# Schematic_Rev2.net
KiCad netlist of a schematic drawn in Altium Designer
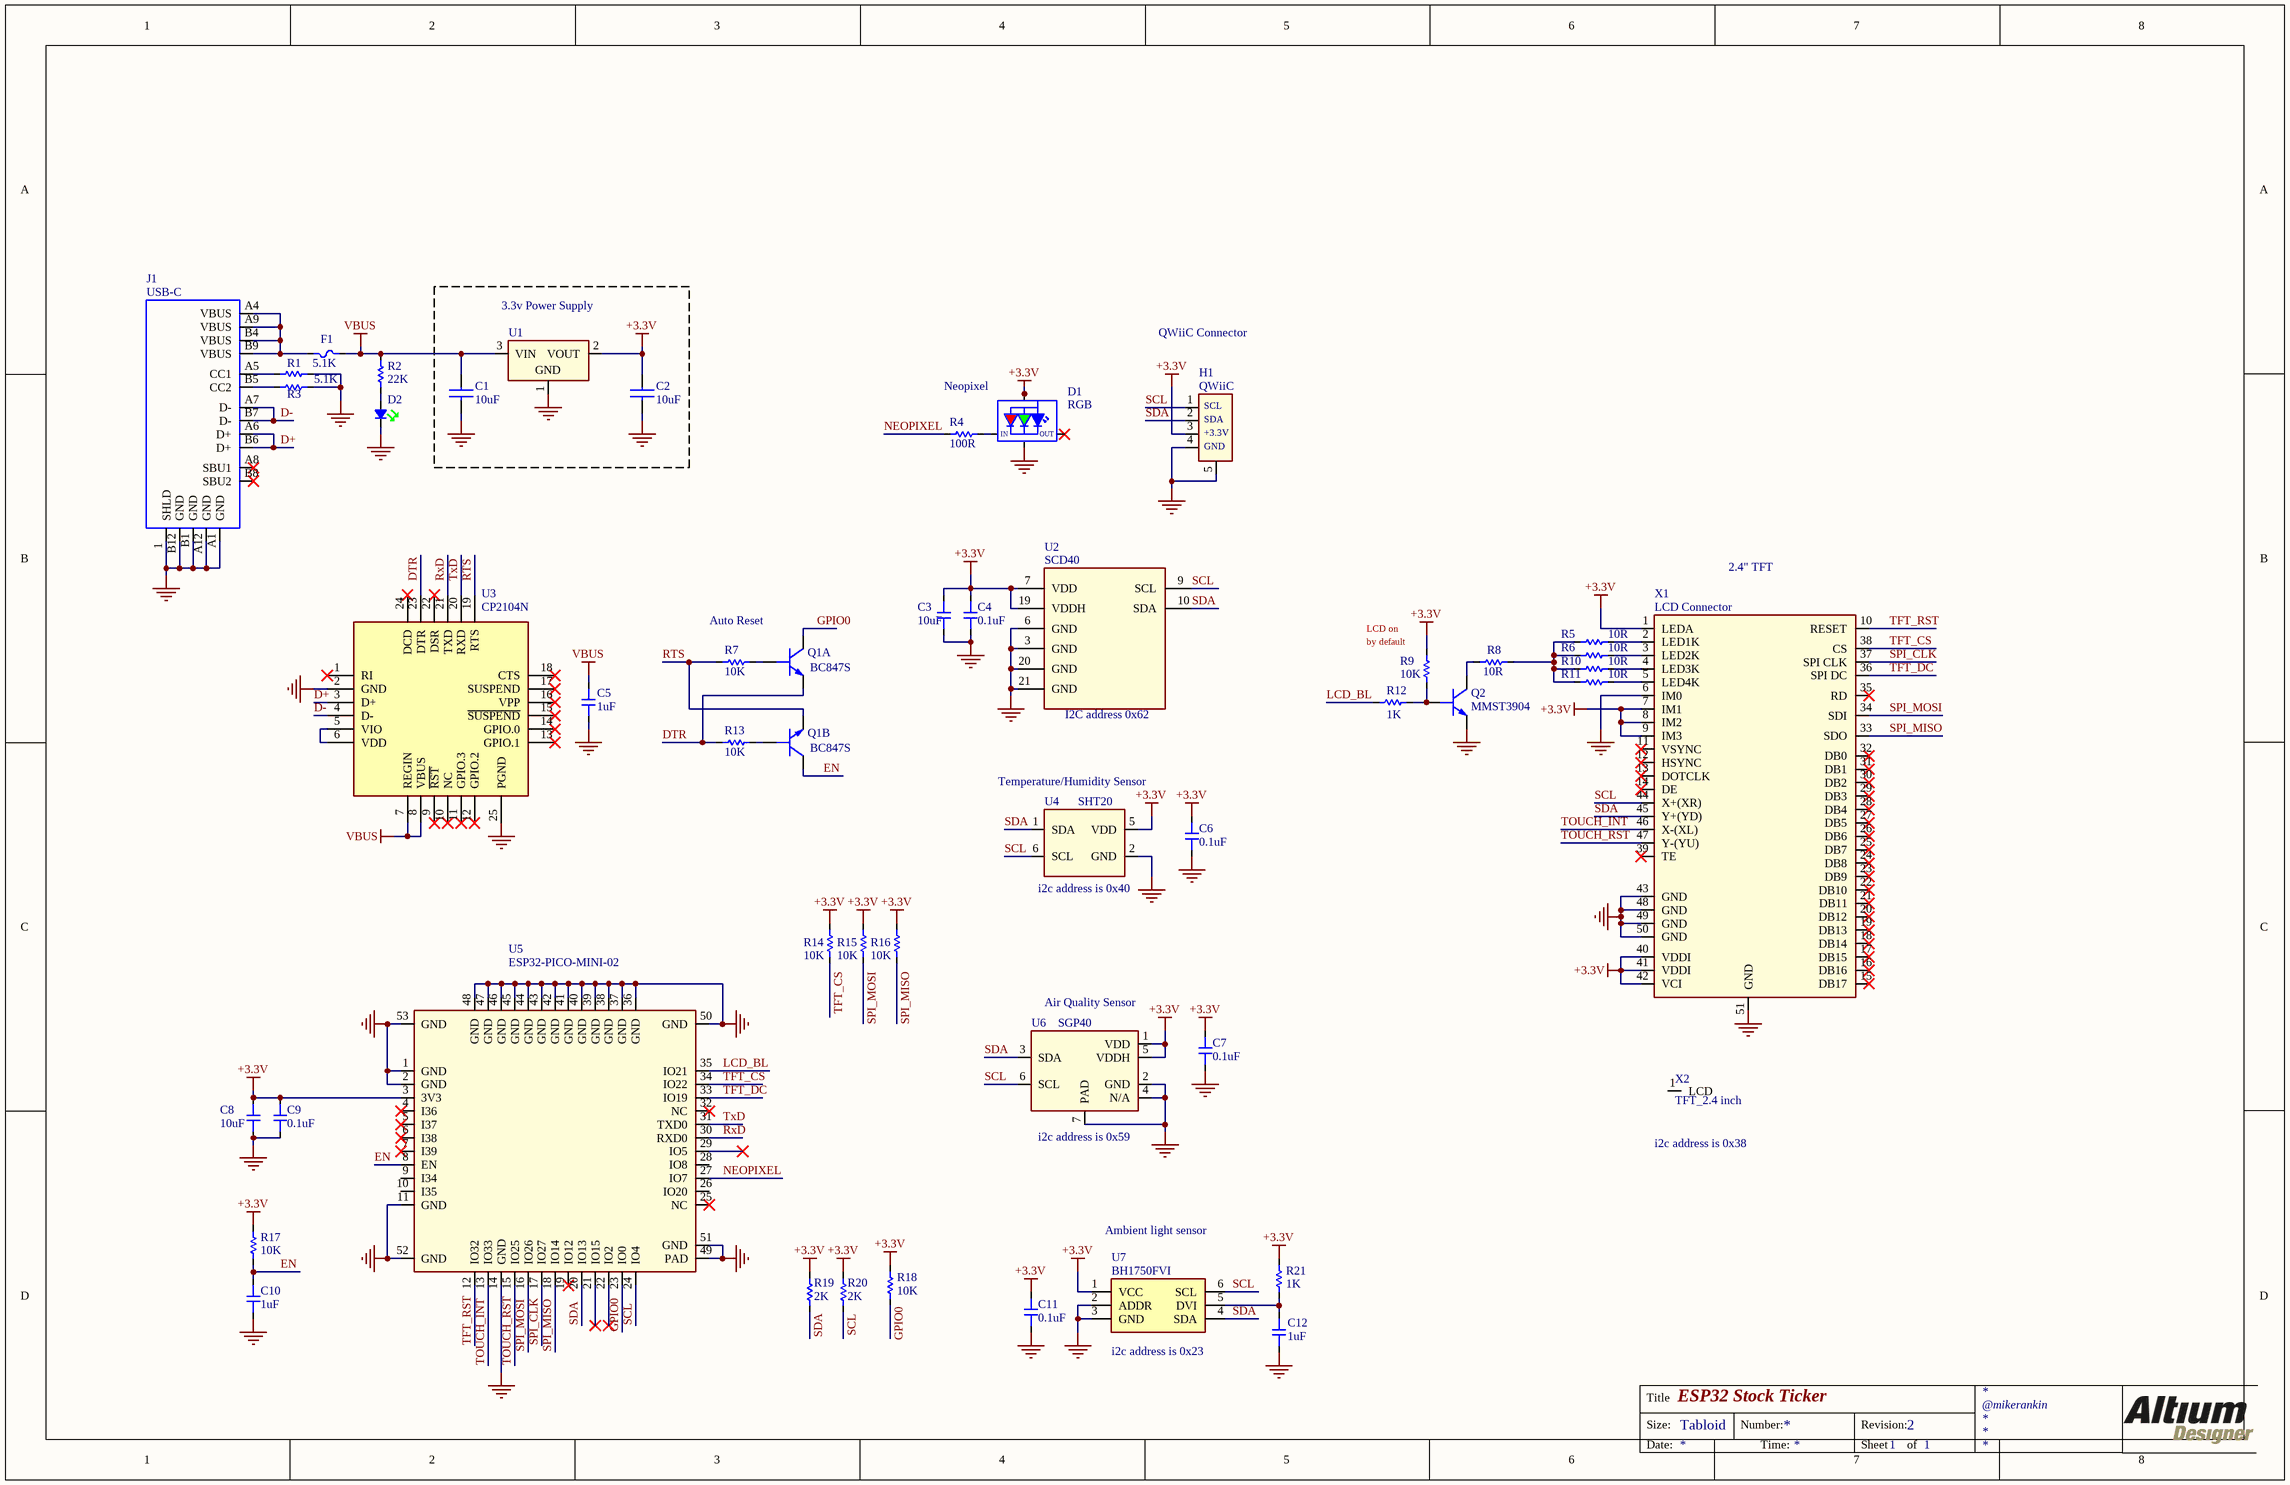
[diagram p0: Schematic_Rev2.SchDoc]

(export (version "E")
  (design (tool "Eeschema 10.0.6"))
  (components
    (comp (ref "C1")
      (value "10uF")
      (footprint "CAPC2012X140N")
      (description "CAP 10uF 16V 0805")
      (fields (field (name "PART_NUMBER") "C162317") (field (name "MANUFACTURER") "Murata"))
      (libsource (lib "MAR") (part "CAP_0805"))
    )
    (comp (ref "C2")
      (value "10uF")
      (footprint "CAPC2012X140N")
      (description "CAP 10uF 16V 0805")
      (fields (field (name "PART_NUMBER") "C162317") (field (name "MANUFACTURER") "Murata"))
      (libsource (lib "MAR") (part "CAP_0805"))
    )
    (comp (ref "C3")
      (value "10uF")
      (footprint "CAPC2012X140N")
      (description "CAP 10uF 50V 0805")
      (libsource (lib "") (part "CAP_0805_1"))
    )
    (comp (ref "C4")
      (value "0.1uF")
      (footprint "CAPC1608X09L")
      (description "CAP 0.1uF 0603")
      (libsource (lib "MAR") (part "CAP_0603"))
    )
    (comp (ref "C5")
      (value "1uF")
      (footprint "CAPC1005X56N")
      (description "CAP 1uF 0402")
      (libsource (lib "MAR") (part "CAP_0402"))
    )
    (comp (ref "C6")
      (value "0.1uF")
      (footprint "CAPC1005X56N")
      (description "CAP 0.1uF 0402")
      (libsource (lib "MAR") (part "CAP_0402"))
    )
    (comp (ref "C7")
      (value "0.1uF")
      (footprint "CAPC1005X56N")
      (description "CAP 0.1uF 0402")
      (libsource (lib "MAR") (part "CAP_0402"))
    )
    (comp (ref "C8")
      (value "10uF")
      (footprint "CAPC2012X140N")
      (description "CAP 10uF 0805")
      (libsource (lib "") (part "CAP_0805_1"))
    )
    (comp (ref "C9")
      (value "0.1uF")
      (footprint "CAPC1608X09L")
      (description "CAP 0.1uF 0603")
      (libsource (lib "MAR") (part "CAP_0603"))
    )
    (comp (ref "C10")
      (value "1uF")
      (footprint "CAPC1005X56N")
      (description "CAP 1uF 0402")
      (libsource (lib "MAR") (part "CAP_0402"))
    )
    (comp (ref "C11")
      (value "0.1uF")
      (footprint "CAPC1005X56N")
      (description "CAP 0.1uF 0402")
      (libsource (lib "MAR") (part "CAP_0402"))
    )
    (comp (ref "C12")
      (value "1uF")
      (footprint "CAPC1005X56N")
      (description "CAP 1uF 0402")
      (libsource (lib "MAR") (part "CAP_0402"))
    )
    (comp (ref "D1")
      (value "RGB")
      (footprint "SK6805-EC14")
      (description "LED,RGB,NEOPIXEL,SK6805-EC14")
      (fields (field (name "PART_NUMBER") "C2909055") (field (name "MANUFACTURER") "OPSCO"))
      (libsource (lib "MAR") (part "SK6805-EC14"))
    )
    (comp (ref "D2")
      (value "Green Led")
      (footprint "LED1005X40N-Green")
      (description "LED Green 0402")
      (fields (field (name "PART_NUMBER") "C74338"))
      (libsource (lib "MAR") (part "LED_0402_SMALL_GREEN"))
    )
    (comp (ref "F1")
      (value "TLC-PSMD050")
      (footprint "PTC2012X70L")
      (description "PTC FUSE 500mA hold, 1A trip 0805 SMD")
      (fields (field (name "MANUFACTURER") "TLC") (field (name "LCSC_PART_NUMBER") "C261942"))
      (libsource (lib "MAR") (part "PTC_FUSE"))
    )
    (comp (ref "H1")
      (value "QWiiC")
      (footprint "SM04B-SRSS-TB")
      (description "CONN HEADER 4POS .100 R/A QWIIC")
      (fields (field (name "MANUFACTURER") "JST") (field (name "PART_NUMBER") "SM04B-SRSS-TB(LF)(SN)"))
      (libsource (lib "MAR") (part "SM04B-SRSS-TB"))
    )
    (comp (ref "J1")
      (value "USB-C")
      (footprint "TYPE-C-31-M-12")
      (description "CONN RECPT USB-C")
      (fields (field (name "MANUFACTURER") "KHE") (field (name "PART_NUMBER") "C165948"))
      (libsource (lib "MAR") (part "USB-C"))
    )
    (comp (ref "Q1")
      (value "BC847S")
      (footprint "SOT65P210X110-6N")
      (description "TRANS 2NPN 44V 0.1A SC-70-6")
      (fields (field (name "MANUFACTURER") "Changjiang") (field (name "PART_NUMBER") "BC847S"))
      (libsource (lib "MAR") (part "BC847S"))
    )
    (comp (ref "Q2")
      (value "MMST3904")
      (footprint "SC-70")
      (description "TRANSISTOR NPN GP 40V SC-70")
      (fields (field (name "MANUFACTURER") "Changjiang") (field (name "PART_NUMBER") "C54879"))
      (libsource (lib "MAR") (part "MMST3904"))
    )
    (comp (ref "R1")
      (value "5.1K")
      (footprint "RESC1005X40L (0402 FOOTPRINT)")
      (description "RES 5.1K 0402")
      (libsource (lib "MAR") (part "RES_0603"))
    )
    (comp (ref "R2")
      (value "22K")
      (footprint "RESC1005X40L (0402 FOOTPRINT)")
      (description "RES 22K 0402")
      (fields (field (name "MANUFACTURER") "LIZ Elec") (field (name "PART_NUMBER") "C100310"))
      (libsource (lib "MAR") (part "RES_0603"))
    )
    (comp (ref "R3")
      (value "5.1K")
      (footprint "RESC1005X40L (0402 FOOTPRINT)")
      (description "RES 5.1K 0402")
      (libsource (lib "MAR") (part "RES_0603"))
    )
    (comp (ref "R4")
      (value "100R")
      (footprint "RESC1005X40L (0402 FOOTPRINT)")
      (description "RES 100R 0402")
      (libsource (lib "MAR") (part "RES_0402"))
    )
    (comp (ref "R5")
      (value "10R")
      (footprint "RESC1005X40L (0402 FOOTPRINT)")
      (description "RES 10R 0402")
      (libsource (lib "MAR") (part "RES_0402"))
    )
    (comp (ref "R6")
      (value "10R")
      (footprint "RESC1005X40L (0402 FOOTPRINT)")
      (description "RES 10R 0402")
      (libsource (lib "MAR") (part "RES_0402"))
    )
    (comp (ref "R7")
      (value "10K")
      (footprint "RESC1005X40L (0402 FOOTPRINT)")
      (description "RES 10K 0402")
      (libsource (lib "MAR") (part "RES_0402"))
    )
    (comp (ref "R8")
      (value "10R")
      (footprint "RESC1005X40L (0402 FOOTPRINT)")
      (description "RES 10R 0402")
      (libsource (lib "MAR") (part "RES_0402"))
    )
    (comp (ref "R9")
      (value "10K")
      (footprint "RESC1005X40L (0402 FOOTPRINT)")
      (description "RES 10K 0402")
      (libsource (lib "MAR") (part "RES_0402"))
    )
    (comp (ref "R10")
      (value "10R")
      (footprint "RESC1005X40L (0402 FOOTPRINT)")
      (description "RES 10R 0402")
      (libsource (lib "MAR") (part "RES_0402"))
    )
    (comp (ref "R11")
      (value "10R")
      (footprint "RESC1005X40L (0402 FOOTPRINT)")
      (description "RES 10R 0402")
      (libsource (lib "MAR") (part "RES_0402"))
    )
    (comp (ref "R12")
      (value "1K")
      (footprint "RESC1005X40L (0402 FOOTPRINT)")
      (description "RES 1K 0402")
      (libsource (lib "MAR") (part "RES_0402"))
    )
    (comp (ref "R13")
      (value "10K")
      (footprint "RESC1005X40L (0402 FOOTPRINT)")
      (description "RES 10K 0402")
      (libsource (lib "MAR") (part "RES_0402"))
    )
    (comp (ref "R14")
      (value "10K")
      (footprint "RESC1005X40L (0402 FOOTPRINT)")
      (description "RES 10K 0402")
      (libsource (lib "MAR") (part "RES_0402"))
    )
    (comp (ref "R15")
      (value "10K")
      (footprint "RESC1005X40L (0402 FOOTPRINT)")
      (description "RES 10K 0402")
      (libsource (lib "MAR") (part "RES_0402"))
    )
    (comp (ref "R16")
      (value "10K")
      (footprint "RESC1005X40L (0402 FOOTPRINT)")
      (description "RES 10K 0402")
      (libsource (lib "MAR") (part "RES_0402"))
    )
    (comp (ref "R17")
      (value "10K")
      (footprint "RESC1005X40L (0402 FOOTPRINT)")
      (description "RES 10K 0402")
      (libsource (lib "MAR") (part "RES_0402"))
    )
    (comp (ref "R18")
      (value "10K")
      (footprint "RESC1005X40L (0402 FOOTPRINT)")
      (description "RES 10K 0402")
      (libsource (lib "MAR") (part "RES_0402"))
    )
    (comp (ref "R19")
      (value "2K")
      (footprint "RESC1005X40L (0402 FOOTPRINT)")
      (description "RES 2K 0402")
      (libsource (lib "MAR") (part "RES_0402"))
    )
    (comp (ref "R20")
      (value "2K")
      (footprint "RESC1005X40L (0402 FOOTPRINT)")
      (description "RES 2K 0402")
      (libsource (lib "MAR") (part "RES_0402"))
    )
    (comp (ref "R21")
      (value "1K")
      (footprint "RESC1005X40L (0402 FOOTPRINT)")
      (description "RES 1K 0402")
      (libsource (lib "MAR") (part "RES_0402"))
    )
    (comp (ref "U1")
      (value "NCP1117LPST33T3G")
      (footprint "SOT230P700X180-4N")
      (description "IC REG LDO 3.3V 1A SOT223-3")
      (fields (field (name "MANUFACTURER") "ON Semi"))
      (libsource (lib "MAR") (part "NCP1117LPST33T3G"))
    )
    (comp (ref "U2")
      (value "SCD40")
      (footprint "SCD40")
      (description "CO2 SENSOR 50 PPM I2C SMD")
      (fields (field (name "MANUFACTURER") "Sensirion"))
      (libsource (lib "MAR") (part "SCD40"))
    )
    (comp (ref "U3")
      (value "CP2104N")
      (footprint "24-QFN")
      (description "IC BRIDGE USB TO UART 24QFN")
      (fields (field (name "MANUFACTURER") "Silicon Labs") (field (name "PART_NUMBER") "C47742"))
      (libsource (lib "MAR") (part "CP2104N"))
    )
    (comp (ref "U4")
      (value "SHT20")
      (footprint "DFN-6 (3mm X 3mm)")
      (description "SENSOR HUMID/TEMP 3V I2C 3% SMD")
      (fields (field (name "MANUFACTURER") "Sensirion AG"))
      (libsource (lib "MAR") (part "SHT20"))
    )
    (comp (ref "U5")
      (value "ESP32-PICO-MINI-02")
      (footprint "ESP32-PICO-MINI-02")
      (description "WIFI/Bluetooth, Mini Module")
      (fields (field (name "MANUFACTURER") "Espressif"))
      (libsource (lib "MAR") (part "ESP32-PICO-MINI-02"))
    )
    (comp (ref "U6")
      (value "SGP40")
      (footprint "DFN-6 (2.45mm X 2.45mm)")
      (description "AIR QUALITY GAS SENSOR FOR VOC'S")
      (fields (field (name "MANUFACTURER") "Sensirion AG") (field (name "PART_NUMBER") "SGP40-D-R4"))
      (libsource (lib "MAR") (part "SGP40"))
    )
    (comp (ref "U7")
      (value "BH1750FVI")
      (footprint "WSOF-6")
      (description "Optical Sensor Ambient I2C 6-SMD")
      (fields (field (name "MANUFACTURER") "Rohm") (field (name "PART_NUMBER") "C78960"))
      (libsource (lib "MAR") (part "BH1750FVI"))
    )
    (comp (ref "X1")
      (value "LCD Connector")
      (footprint "ER-CON50HT")
      (description "FFC, FPC 50 pin 0.5mm Connector for 2.4\" TFT")
      (fields (field (name "PART_NUMBER") "C397332") (field (name "MANUFACTURER") "XKB"))
      (libsource (lib "MAR") (part "FFC, FPC 50 pin 0.5mm Con 2.4{dblquote} TFT"))
    )
    (comp (ref "X2")
      (value "TFT_2.4 inch")
      (description "2.4 INCH TFT GLASS COLOR")
      (fields (field (name "PART_NUMBER") "ER-TFT024-3") (field (name "MANUFACTURER") "BuyDisplay.com"))
      (libsource (lib "MAR") (part "TFT_GLASS 2.4 INCH COLOR"))
    )
  )
  (nets
    (net (code "1") (name "+3.3V") (class "Default")
      (node (ref "C11") (pin "1") (pintype "passive"))
      (node (ref "C2") (pin "1") (pinfunction "1_1") (pintype "passive"))
      (node (ref "C3") (pin "1") (pintype "passive"))
      (node (ref "C4") (pin "1") (pintype "passive"))
      (node (ref "C6") (pin "1") (pintype "passive"))
      (node (ref "C7") (pin "1") (pintype "passive"))
      (node (ref "C8") (pin "1") (pintype "passive"))
      (node (ref "C9") (pin "1") (pintype "passive"))
      (node (ref "D1") (pin "1") (pinfunction "VDD_1") (pintype "passive"))
      (node (ref "H1") (pin "3") (pintype "passive"))
      (node (ref "R14") (pin "1") (pintype "passive"))
      (node (ref "R15") (pin "1") (pintype "passive"))
      (node (ref "R16") (pin "1") (pintype "passive"))
      (node (ref "R17") (pin "2") (pintype "passive"))
      (node (ref "R18") (pin "2") (pintype "passive"))
      (node (ref "R19") (pin "1") (pintype "passive"))
      (node (ref "R20") (pin "1") (pintype "passive"))
      (node (ref "R21") (pin "2") (pintype "passive"))
      (node (ref "R9") (pin "1") (pintype "passive"))
      (node (ref "U1") (pin "2") (pinfunction "VOUT_2") (pintype "power_in"))
      (node (ref "U2") (pin "19") (pinfunction "VDDH_19") (pintype "power_in"))
      (node (ref "U2") (pin "7") (pinfunction "VDD_7") (pintype "power_in"))
      (node (ref "U4") (pin "5") (pinfunction "VDD_5") (pintype "power_in"))
      (node (ref "U5") (pin "3") (pinfunction "3V3_3") (pintype "power_in"))
      (node (ref "U6") (pin "1") (pinfunction "VDD_1") (pintype "power_in"))
      (node (ref "U6") (pin "5") (pinfunction "VDDH_5") (pintype "power_in"))
      (node (ref "U7") (pin "1") (pinfunction "VCC_1") (pintype "power_in"))
      (node (ref "X1") (pin "1") (pinfunction "LEDA_1") (pintype "passive"))
      (node (ref "X1") (pin "40") (pinfunction "VDDI_40") (pintype "power_in"))
      (node (ref "X1") (pin "41") (pinfunction "VDDI_41") (pintype "open_emitter"))
      (node (ref "X1") (pin "42") (pinfunction "VCI_42") (pintype "power_in"))
      (node (ref "X1") (pin "7") (pinfunction "IM1_7") (pintype "passive"))
      (node (ref "X1") (pin "8") (pinfunction "IM2_8") (pintype "passive"))
      (node (ref "X1") (pin "9") (pinfunction "IM3_9") (pintype "passive"))
    )
    (net (code "2") (name "/D+") (class "Default")
      (node (ref "J1") (pin "A6") (pinfunction "D+_A6") (pintype "power_in"))
      (node (ref "J1") (pin "B6") (pinfunction "D+_B6") (pintype "power_in"))
      (node (ref "U3") (pin "3") (pinfunction "D+_3") (pintype "passive"))
    )
    (net (code "3") (name "/D-") (class "Default")
      (node (ref "J1") (pin "A7") (pinfunction "D-_A7") (pintype "power_in"))
      (node (ref "J1") (pin "B7") (pinfunction "D-_B7") (pintype "power_in"))
      (node (ref "U3") (pin "4") (pinfunction "D-_4") (pintype "passive"))
    )
    (net (code "4") (name "/DTR") (class "Default")
      (node (ref "Q1") (pin "1") (pinfunction "E1_1") (pintype "passive"))
      (node (ref "R13") (pin "2") (pintype "passive"))
      (node (ref "U3") (pin "23") (pinfunction "DTR_23") (pintype "passive"))
    )
    (net (code "5") (name "/EN") (class "Default")
      (node (ref "C10") (pin "1") (pintype "passive"))
      (node (ref "Q1") (pin "3") (pinfunction "C2_3") (pintype "passive"))
      (node (ref "R17") (pin "1") (pintype "passive"))
      (node (ref "U5") (pin "8") (pinfunction "EN_8") (pintype "passive"))
    )
    (net (code "6") (name "/GPIO0") (class "Default")
      (node (ref "Q1") (pin "6") (pinfunction "C1_6") (pintype "passive"))
      (node (ref "R18") (pin "1") (pintype "passive"))
      (node (ref "U5") (pin "23") (pinfunction "IO0_23") (pintype "passive"))
    )
    (net (code "7") (name "/LCD_BL") (class "Default")
      (node (ref "R12") (pin "2") (pintype "passive"))
      (node (ref "U5") (pin "35") (pinfunction "IO21_35") (pintype "passive"))
    )
    (net (code "8") (name "/NEOPIXEL") (class "Default")
      (node (ref "R4") (pin "2") (pintype "passive"))
      (node (ref "U5") (pin "27") (pinfunction "IO7_27") (pintype "passive"))
    )
    (net (code "9") (name "/RTS") (class "Default")
      (node (ref "Q1") (pin "4") (pinfunction "E2_4") (pintype "passive"))
      (node (ref "R7") (pin "2") (pintype "passive"))
      (node (ref "U3") (pin "19") (pinfunction "RTS_19") (pintype "passive"))
    )
    (net (code "10") (name "/RxD") (class "Default")
      (node (ref "U3") (pin "21") (pinfunction "TXD_21") (pintype "passive"))
      (node (ref "U5") (pin "30") (pinfunction "RXD0_30") (pintype "passive"))
    )
    (net (code "11") (name "/SCL") (class "Default")
      (node (ref "H1") (pin "1") (pintype "passive"))
      (node (ref "R20") (pin "2") (pintype "passive"))
      (node (ref "U2") (pin "9") (pinfunction "SCL_9") (pintype "passive"))
      (node (ref "U4") (pin "6") (pinfunction "SCL_6") (pintype "passive"))
      (node (ref "U5") (pin "24") (pinfunction "IO4_24") (pintype "passive"))
      (node (ref "U6") (pin "6") (pinfunction "SCL_6") (pintype "passive"))
      (node (ref "U7") (pin "6") (pinfunction "SCL_6") (pintype "passive"))
      (node (ref "X1") (pin "44") (pinfunction "X+(XR)_44") (pintype "passive"))
    )
    (net (code "12") (name "/SDA") (class "Default")
      (node (ref "H1") (pin "2") (pintype "passive"))
      (node (ref "R19") (pin "2") (pintype "passive"))
      (node (ref "U2") (pin "10") (pinfunction "SDA_10") (pintype "passive"))
      (node (ref "U4") (pin "1") (pinfunction "SDA_1") (pintype "passive"))
      (node (ref "U5") (pin "20") (pinfunction "IO13_20") (pintype "passive"))
      (node (ref "U6") (pin "3") (pinfunction "SDA_3") (pintype "passive"))
      (node (ref "U7") (pin "4") (pinfunction "SDA_4") (pintype "passive"))
      (node (ref "X1") (pin "45") (pinfunction "Y+(YD)_45") (pintype "passive"))
    )
    (net (code "13") (name "/SPI_CLK") (class "Default")
      (node (ref "U5") (pin "17") (pinfunction "IO27_17") (pintype "passive"))
      (node (ref "X1") (pin "37") (pinfunction "SPI_CLK_37") (pintype "passive"))
    )
    (net (code "14") (name "/SPI_MISO") (class "Default")
      (node (ref "R16") (pin "2") (pintype "passive"))
      (node (ref "U5") (pin "18") (pinfunction "IO14_18") (pintype "passive"))
      (node (ref "X1") (pin "33") (pinfunction "SDO_33") (pintype "passive"))
    )
    (net (code "15") (name "/SPI_MOSI") (class "Default")
      (node (ref "R15") (pin "2") (pintype "passive"))
      (node (ref "U5") (pin "16") (pinfunction "IO26_16") (pintype "passive"))
      (node (ref "X1") (pin "34") (pinfunction "SDI_34") (pintype "passive"))
    )
    (net (code "16") (name "/TFT_CS") (class "Default")
      (node (ref "R14") (pin "2") (pintype "passive"))
      (node (ref "U5") (pin "34") (pinfunction "IO22_34") (pintype "passive"))
      (node (ref "X1") (pin "38") (pinfunction "CS_38") (pintype "passive"))
    )
    (net (code "17") (name "/TFT_DC") (class "Default")
      (node (ref "U5") (pin "33") (pinfunction "IO19_33") (pintype "passive"))
      (node (ref "X1") (pin "36") (pinfunction "SPI_DC_36") (pintype "passive"))
    )
    (net (code "18") (name "/TFT_RST") (class "Default")
      (node (ref "U5") (pin "12") (pinfunction "IO32_12") (pintype "passive"))
      (node (ref "X1") (pin "10") (pinfunction "RESET_10") (pintype "passive"))
    )
    (net (code "19") (name "/TOUCH_INT") (class "Default")
      (node (ref "U5") (pin "13") (pinfunction "IO33_13") (pintype "passive"))
      (node (ref "X1") (pin "46") (pinfunction "X-(XL)_46") (pintype "passive"))
    )
    (net (code "20") (name "/TOUCH_RST") (class "Default")
      (node (ref "U5") (pin "15") (pinfunction "IO25_15") (pintype "passive"))
      (node (ref "X1") (pin "47") (pinfunction "Y-(YU)_47") (pintype "passive"))
    )
    (net (code "21") (name "/TxD") (class "Default")
      (node (ref "U3") (pin "20") (pinfunction "RXD_20") (pintype "passive"))
      (node (ref "U5") (pin "31") (pinfunction "TXD0_31") (pintype "passive"))
    )
    (net (code "22") (name "GND") (class "Default")
      (node (ref "C1") (pin "2") (pinfunction "2_2") (pintype "passive"))
      (node (ref "C10") (pin "2") (pintype "passive"))
      (node (ref "C11") (pin "2") (pintype "passive"))
      (node (ref "C12") (pin "1") (pintype "passive"))
      (node (ref "C2") (pin "2") (pinfunction "2_2") (pintype "passive"))
      (node (ref "C3") (pin "2") (pintype "passive"))
      (node (ref "C4") (pin "2") (pintype "passive"))
      (node (ref "C5") (pin "1") (pintype "passive"))
      (node (ref "C6") (pin "2") (pintype "passive"))
      (node (ref "C7") (pin "2") (pintype "passive"))
      (node (ref "C8") (pin "2") (pintype "passive"))
      (node (ref "C9") (pin "2") (pintype "passive"))
      (node (ref "D1") (pin "3") (pinfunction "GND_3") (pintype "passive"))
      (node (ref "D2") (pin "1") (pintype "passive"))
      (node (ref "H1") (pin "4") (pintype "passive"))
      (node (ref "H1") (pin "5") (pintype "passive"))
      (node (ref "J1") (pin "1") (pinfunction "SHLD_1") (pintype "power_in"))
      (node (ref "J1") (pin "A1") (pinfunction "GND_A1") (pintype "power_in"))
      (node (ref "J1") (pin "A12") (pinfunction "GND_A12") (pintype "power_in"))
      (node (ref "J1") (pin "B1") (pinfunction "GND_B1") (pintype "power_in"))
      (node (ref "J1") (pin "B12") (pinfunction "GND_B12") (pintype "passive"))
      (node (ref "Q2") (pin "2") (pinfunction "E_2") (pintype "passive"))
      (node (ref "R1") (pin "2") (pintype "passive"))
      (node (ref "R3") (pin "2") (pintype "passive"))
      (node (ref "U1") (pin "1") (pinfunction "GND_1") (pintype "power_in"))
      (node (ref "U2") (pin "20") (pinfunction "GND_20") (pintype "power_in"))
      (node (ref "U2") (pin "21") (pinfunction "GND_21") (pintype "power_in"))
      (node (ref "U2") (pin "3") (pinfunction "GND_3") (pintype "power_in"))
      (node (ref "U2") (pin "6") (pinfunction "GND_6") (pintype "power_in"))
      (node (ref "U3") (pin "2") (pinfunction "GND_2") (pintype "power_in"))
      (node (ref "U3") (pin "25") (pinfunction "PGND_25") (pintype "passive"))
      (node (ref "U4") (pin "2") (pinfunction "GND_2") (pintype "power_in"))
      (node (ref "U5") (pin "1") (pinfunction "GND_1") (pintype "power_in"))
      (node (ref "U5") (pin "11") (pinfunction "GND_11") (pintype "power_in"))
      (node (ref "U5") (pin "14") (pinfunction "GND_14") (pintype "power_in"))
      (node (ref "U5") (pin "2") (pinfunction "GND_2") (pintype "power_in"))
      (node (ref "U5") (pin "36") (pinfunction "GND_36") (pintype "power_in"))
      (node (ref "U5") (pin "37") (pinfunction "GND_37") (pintype "power_in"))
      (node (ref "U5") (pin "38") (pinfunction "GND_38") (pintype "power_in"))
      (node (ref "U5") (pin "39") (pinfunction "GND_39") (pintype "power_in"))
      (node (ref "U5") (pin "40") (pinfunction "GND_40") (pintype "power_in"))
      (node (ref "U5") (pin "41") (pinfunction "GND_41") (pintype "power_in"))
      (node (ref "U5") (pin "42") (pinfunction "GND_42") (pintype "power_in"))
      (node (ref "U5") (pin "43") (pinfunction "GND_43") (pintype "power_in"))
      (node (ref "U5") (pin "44") (pinfunction "GND_44") (pintype "power_in"))
      (node (ref "U5") (pin "45") (pinfunction "GND_45") (pintype "power_in"))
      (node (ref "U5") (pin "46") (pinfunction "GND_46") (pintype "power_in"))
      (node (ref "U5") (pin "47") (pinfunction "GND_47") (pintype "power_in"))
      (node (ref "U5") (pin "48") (pinfunction "GND_48") (pintype "power_in"))
      (node (ref "U5") (pin "49") (pinfunction "PAD_49") (pintype "power_in"))
      (node (ref "U5") (pin "50") (pinfunction "GND_50") (pintype "power_in"))
      (node (ref "U5") (pin "51") (pinfunction "GND_51") (pintype "power_in"))
      (node (ref "U5") (pin "52") (pinfunction "GND_52") (pintype "power_in"))
      (node (ref "U5") (pin "53") (pinfunction "GND_53") (pintype "power_in"))
      (node (ref "U6") (pin "2") (pinfunction "GND_2") (pintype "power_in"))
      (node (ref "U6") (pin "4") (pinfunction "N/A_4") (pintype "passive"))
      (node (ref "U6") (pin "7") (pinfunction "PAD_7") (pintype "passive"))
      (node (ref "U7") (pin "2") (pinfunction "ADDR_2") (pintype "passive"))
      (node (ref "U7") (pin "3") (pinfunction "GND_3") (pintype "power_in"))
      (node (ref "X1") (pin "43") (pinfunction "GND_43") (pintype "power_in"))
      (node (ref "X1") (pin "48") (pinfunction "GND_48") (pintype "power_in"))
      (node (ref "X1") (pin "49") (pinfunction "GND_49") (pintype "power_in"))
      (node (ref "X1") (pin "50") (pinfunction "GND_50") (pintype "power_in"))
      (node (ref "X1") (pin "51") (pinfunction "GND_51") (pintype "power_in"))
      (node (ref "X1") (pin "6") (pinfunction "IM0_6") (pintype "passive"))
    )
    (net (code "23") (name "Net-(D1-DIN)") (class "Default")
      (node (ref "D1") (pin "4") (pinfunction "DIN_4") (pintype "passive"))
      (node (ref "R4") (pin "1") (pintype "passive"))
    )
    (net (code "24") (name "Net-(D2-Pad2)") (class "Default")
      (node (ref "D2") (pin "2") (pintype "passive"))
      (node (ref "R2") (pin "1") (pintype "passive"))
    )
    (net (code "25") (name "Net-(F1-Pad2)") (class "Default")
      (node (ref "F1") (pin "2") (pintype "passive"))
      (node (ref "J1") (pin "A4") (pinfunction "VBUS_A4") (pintype "passive"))
      (node (ref "J1") (pin "A9") (pinfunction "VBUS_A9") (pintype "power_in"))
      (node (ref "J1") (pin "B4") (pinfunction "VBUS_B4") (pintype "power_in"))
      (node (ref "J1") (pin "B9") (pinfunction "VBUS_B9") (pintype "passive"))
    )
    (net (code "26") (name "Net-(J1-CC1)") (class "Default")
      (node (ref "J1") (pin "A5") (pinfunction "CC1_A5") (pintype "power_in"))
      (node (ref "R1") (pin "1") (pintype "passive"))
    )
    (net (code "27") (name "Net-(J1-CC2)") (class "Default")
      (node (ref "J1") (pin "B5") (pinfunction "CC2_B5") (pintype "power_in"))
      (node (ref "R3") (pin "1") (pintype "passive"))
    )
    (net (code "28") (name "Net-(Q1A-B1)") (class "Default")
      (node (ref "Q1") (pin "2") (pinfunction "B1_2") (pintype "passive"))
      (node (ref "R7") (pin "1") (pintype "passive"))
    )
    (net (code "29") (name "Net-(Q1B-B2)") (class "Default")
      (node (ref "Q1") (pin "5") (pinfunction "B2_5") (pintype "passive"))
      (node (ref "R13") (pin "1") (pintype "passive"))
    )
    (net (code "30") (name "Net-(Q2-B)") (class "Default")
      (node (ref "Q2") (pin "1") (pinfunction "B_1") (pintype "passive"))
      (node (ref "R12") (pin "1") (pintype "passive"))
      (node (ref "R9") (pin "2") (pintype "passive"))
    )
    (net (code "31") (name "Net-(Q2-C)") (class "Default")
      (node (ref "Q2") (pin "3") (pinfunction "C_3") (pintype "passive"))
      (node (ref "R8") (pin "2") (pintype "passive"))
    )
    (net (code "32") (name "Net-(R10-Pad2)") (class "Default")
      (node (ref "R10") (pin "2") (pintype "passive"))
      (node (ref "R11") (pin "2") (pintype "passive"))
      (node (ref "R5") (pin "2") (pintype "passive"))
      (node (ref "R6") (pin "2") (pintype "passive"))
      (node (ref "R8") (pin "1") (pintype "passive"))
    )
    (net (code "33") (name "Net-(U3-VDD)") (class "Default")
      (node (ref "U3") (pin "5") (pinfunction "VIO_5") (pintype "power_in"))
      (node (ref "U3") (pin "6") (pinfunction "VDD_6") (pintype "power_in"))
    )
    (net (code "34") (name "Net-(U7-DVI)") (class "Default")
      (node (ref "C12") (pin "2") (pintype "passive"))
      (node (ref "R21") (pin "1") (pintype "passive"))
      (node (ref "U7") (pin "5") (pinfunction "DVI_5") (pintype "passive"))
    )
    (net (code "35") (name "Net-(X1-LED1K)") (class "Default")
      (node (ref "R5") (pin "1") (pintype "passive"))
      (node (ref "X1") (pin "2") (pinfunction "LED1K_2") (pintype "passive"))
    )
    (net (code "36") (name "Net-(X1-LED2K)") (class "Default")
      (node (ref "R6") (pin "1") (pintype "passive"))
      (node (ref "X1") (pin "3") (pinfunction "LED2K_3") (pintype "passive"))
    )
    (net (code "37") (name "Net-(X1-LED3K)") (class "Default")
      (node (ref "R10") (pin "1") (pintype "passive"))
      (node (ref "X1") (pin "4") (pinfunction "LED3K_4") (pintype "passive"))
    )
    (net (code "38") (name "Net-(X1-LED4K)") (class "Default")
      (node (ref "R11") (pin "1") (pintype "passive"))
      (node (ref "X1") (pin "5") (pinfunction "LED4K_5") (pintype "passive"))
    )
    (net (code "39") (name "VBUS") (class "Default")
      (node (ref "C1") (pin "1") (pinfunction "1_1") (pintype "passive"))
      (node (ref "C5") (pin "2") (pintype "passive"))
      (node (ref "F1") (pin "1") (pintype "passive"))
      (node (ref "R2") (pin "2") (pintype "passive"))
      (node (ref "U1") (pin "3") (pinfunction "VIN_3") (pintype "power_in"))
      (node (ref "U3") (pin "7") (pinfunction "REGIN_7") (pintype "power_in"))
      (node (ref "U3") (pin "8") (pinfunction "VBUS_8") (pintype "power_in"))
    )
    (net (code "40") (name "unconnected-(D1-DOUT-Pad2)") (class "Default")
      (node (ref "D1") (pin "2") (pinfunction "DOUT_2") (pintype "passive+no_connect"))
    )
    (net (code "41") (name "unconnected-(J1-SBU1-PadA8)") (class "Default")
      (node (ref "J1") (pin "A8") (pinfunction "SBU1_A8") (pintype "power_in+no_connect"))
    )
    (net (code "42") (name "unconnected-(J1-SBU2-PadB8)") (class "Default")
      (node (ref "J1") (pin "B8") (pinfunction "SBU2_B8") (pintype "power_in+no_connect"))
    )
    (net (code "43") (name "unconnected-(U3-CTS-Pad18)") (class "Default")
      (node (ref "U3") (pin "18") (pinfunction "CTS_18") (pintype "passive+no_connect"))
    )
    (net (code "44") (name "unconnected-(U3-DCD-Pad24)") (class "Default")
      (node (ref "U3") (pin "24") (pinfunction "DCD_24") (pintype "passive+no_connect"))
    )
    (net (code "45") (name "unconnected-(U3-DSR-Pad22)") (class "Default")
      (node (ref "U3") (pin "22") (pinfunction "DSR_22") (pintype "passive+no_connect"))
    )
    (net (code "46") (name "unconnected-(U3-GPIO.0-Pad14)") (class "Default")
      (node (ref "U3") (pin "14") (pinfunction "GPIO.0_14") (pintype "passive+no_connect"))
    )
    (net (code "47") (name "unconnected-(U3-GPIO.1-Pad13)") (class "Default")
      (node (ref "U3") (pin "13") (pinfunction "GPIO.1_13") (pintype "passive+no_connect"))
    )
    (net (code "48") (name "unconnected-(U3-GPIO.2-Pad12)") (class "Default")
      (node (ref "U3") (pin "12") (pinfunction "GPIO.2_12") (pintype "passive+no_connect"))
    )
    (net (code "49") (name "unconnected-(U3-GPIO.3-Pad11)") (class "Default")
      (node (ref "U3") (pin "11") (pinfunction "GPIO.3_11") (pintype "passive+no_connect"))
    )
    (net (code "50") (name "unconnected-(U3-NC-Pad10)") (class "Default")
      (node (ref "U3") (pin "10") (pinfunction "NC_10") (pintype "passive+no_connect"))
    )
    (net (code "51") (name "unconnected-(U3-RI-Pad1)") (class "Default")
      (node (ref "U3") (pin "1") (pinfunction "RI_1") (pintype "passive+no_connect"))
    )
    (net (code "52") (name "unconnected-(U3-SUSPEND-Pad17)") (class "Default")
      (node (ref "U3") (pin "17") (pinfunction "SUSPEND_17") (pintype "passive+no_connect"))
    )
    (net (code "53") (name "unconnected-(U3-VPP-Pad16)") (class "Default")
      (node (ref "U3") (pin "16") (pinfunction "VPP_16") (pintype "passive+no_connect"))
    )
    (net (code "54") (name "unconnected-(U3-~{RST}-Pad9)") (class "Default")
      (node (ref "U3") (pin "9") (pinfunction "~{RST}_9") (pintype "passive+no_connect"))
    )
    (net (code "55") (name "unconnected-(U3-~{SUSPEND}-Pad15)") (class "Default")
      (node (ref "U3") (pin "15") (pinfunction "~{SUSPEND}_15") (pintype "passive+no_connect"))
    )
    (net (code "56") (name "unconnected-(U5-I34-Pad9)") (class "Default")
      (node (ref "U5") (pin "9") (pinfunction "I34_9") (pintype "passive"))
    )
    (net (code "57") (name "unconnected-(U5-I35-Pad10)") (class "Default")
      (node (ref "U5") (pin "10") (pinfunction "I35_10") (pintype "passive"))
    )
    (net (code "58") (name "unconnected-(U5-I36-Pad4)") (class "Default")
      (node (ref "U5") (pin "4") (pinfunction "I36_4") (pintype "passive+no_connect"))
    )
    (net (code "59") (name "unconnected-(U5-I37-Pad5)") (class "Default")
      (node (ref "U5") (pin "5") (pinfunction "I37_5") (pintype "passive+no_connect"))
    )
    (net (code "60") (name "unconnected-(U5-I38-Pad6)") (class "Default")
      (node (ref "U5") (pin "6") (pinfunction "I38_6") (pintype "passive+no_connect"))
    )
    (net (code "61") (name "unconnected-(U5-I39-Pad7)") (class "Default")
      (node (ref "U5") (pin "7") (pinfunction "I39_7") (pintype "passive+no_connect"))
    )
    (net (code "62") (name "unconnected-(U5-IO2-Pad22)") (class "Default")
      (node (ref "U5") (pin "22") (pinfunction "IO2_22") (pintype "passive+no_connect"))
    )
    (net (code "63") (name "unconnected-(U5-IO5-Pad29)") (class "Default")
      (node (ref "U5") (pin "29") (pinfunction "IO5_29") (pintype "passive+no_connect"))
    )
    (net (code "64") (name "unconnected-(U5-IO8-Pad28)") (class "Default")
      (node (ref "U5") (pin "28") (pinfunction "IO8_28") (pintype "passive"))
    )
    (net (code "65") (name "unconnected-(U5-IO12-Pad19)") (class "Default")
      (node (ref "U5") (pin "19") (pinfunction "IO12_19") (pintype "passive+no_connect"))
    )
    (net (code "66") (name "unconnected-(U5-IO15-Pad21)") (class "Default")
      (node (ref "U5") (pin "21") (pinfunction "IO15_21") (pintype "passive+no_connect"))
    )
    (net (code "67") (name "unconnected-(U5-IO20-Pad26)") (class "Default")
      (node (ref "U5") (pin "26") (pinfunction "IO20_26") (pintype "power_in"))
    )
    (net (code "68") (name "unconnected-(U5-NC-Pad25)") (class "Default")
      (node (ref "U5") (pin "25") (pinfunction "NC_25") (pintype "passive+no_connect"))
    )
    (net (code "69") (name "unconnected-(U5-NC-Pad32)") (class "Default")
      (node (ref "U5") (pin "32") (pinfunction "NC_32") (pintype "passive+no_connect"))
    )
    (net (code "70") (name "unconnected-(X1-DB0-Pad32)") (class "Default")
      (node (ref "X1") (pin "32") (pinfunction "DB0_32") (pintype "passive+no_connect"))
    )
    (net (code "71") (name "unconnected-(X1-DB1-Pad31)") (class "Default")
      (node (ref "X1") (pin "31") (pinfunction "DB1_31") (pintype "passive+no_connect"))
    )
    (net (code "72") (name "unconnected-(X1-DB2-Pad30)") (class "Default")
      (node (ref "X1") (pin "30") (pinfunction "DB2_30") (pintype "passive+no_connect"))
    )
    (net (code "73") (name "unconnected-(X1-DB3-Pad29)") (class "Default")
      (node (ref "X1") (pin "29") (pinfunction "DB3_29") (pintype "passive+no_connect"))
    )
    (net (code "74") (name "unconnected-(X1-DB4-Pad28)") (class "Default")
      (node (ref "X1") (pin "28") (pinfunction "DB4_28") (pintype "passive+no_connect"))
    )
    (net (code "75") (name "unconnected-(X1-DB5-Pad27)") (class "Default")
      (node (ref "X1") (pin "27") (pinfunction "DB5_27") (pintype "passive+no_connect"))
    )
    (net (code "76") (name "unconnected-(X1-DB6-Pad26)") (class "Default")
      (node (ref "X1") (pin "26") (pinfunction "DB6_26") (pintype "passive+no_connect"))
    )
    (net (code "77") (name "unconnected-(X1-DB7-Pad25)") (class "Default")
      (node (ref "X1") (pin "25") (pinfunction "DB7_25") (pintype "passive+no_connect"))
    )
    (net (code "78") (name "unconnected-(X1-DB8-Pad24)") (class "Default")
      (node (ref "X1") (pin "24") (pinfunction "DB8_24") (pintype "passive+no_connect"))
    )
    (net (code "79") (name "unconnected-(X1-DB9-Pad23)") (class "Default")
      (node (ref "X1") (pin "23") (pinfunction "DB9_23") (pintype "passive+no_connect"))
    )
    (net (code "80") (name "unconnected-(X1-DB10-Pad22)") (class "Default")
      (node (ref "X1") (pin "22") (pinfunction "DB10_22") (pintype "passive+no_connect"))
    )
    (net (code "81") (name "unconnected-(X1-DB11-Pad21)") (class "Default")
      (node (ref "X1") (pin "21") (pinfunction "DB11_21") (pintype "passive+no_connect"))
    )
    (net (code "82") (name "unconnected-(X1-DB12-Pad20)") (class "Default")
      (node (ref "X1") (pin "20") (pinfunction "DB12_20") (pintype "passive+no_connect"))
    )
    (net (code "83") (name "unconnected-(X1-DB13-Pad19)") (class "Default")
      (node (ref "X1") (pin "19") (pinfunction "DB13_19") (pintype "passive+no_connect"))
    )
    (net (code "84") (name "unconnected-(X1-DB14-Pad18)") (class "Default")
      (node (ref "X1") (pin "18") (pinfunction "DB14_18") (pintype "passive+no_connect"))
    )
    (net (code "85") (name "unconnected-(X1-DB15-Pad17)") (class "Default")
      (node (ref "X1") (pin "17") (pinfunction "DB15_17") (pintype "passive+no_connect"))
    )
    (net (code "86") (name "unconnected-(X1-DB16-Pad16)") (class "Default")
      (node (ref "X1") (pin "16") (pinfunction "DB16_16") (pintype "passive+no_connect"))
    )
    (net (code "87") (name "unconnected-(X1-DB17-Pad15)") (class "Default")
      (node (ref "X1") (pin "15") (pinfunction "DB17_15") (pintype "passive+no_connect"))
    )
    (net (code "88") (name "unconnected-(X1-DE-Pad14)") (class "Default")
      (node (ref "X1") (pin "14") (pinfunction "DE_14") (pintype "passive+no_connect"))
    )
    (net (code "89") (name "unconnected-(X1-DOTCLK-Pad13)") (class "Default")
      (node (ref "X1") (pin "13") (pinfunction "DOTCLK_13") (pintype "passive+no_connect"))
    )
    (net (code "90") (name "unconnected-(X1-HSYNC-Pad12)") (class "Default")
      (node (ref "X1") (pin "12") (pinfunction "HSYNC_12") (pintype "passive+no_connect"))
    )
    (net (code "91") (name "unconnected-(X1-RD-Pad35)") (class "Default")
      (node (ref "X1") (pin "35") (pinfunction "RD_35") (pintype "passive+no_connect"))
    )
    (net (code "92") (name "unconnected-(X1-TE-Pad39)") (class "Default")
      (node (ref "X1") (pin "39") (pinfunction "TE_39") (pintype "passive+no_connect"))
    )
    (net (code "93") (name "unconnected-(X1-VSYNC-Pad11)") (class "Default")
      (node (ref "X1") (pin "11") (pinfunction "VSYNC_11") (pintype "passive+no_connect"))
    )
    (net (code "94") (name "unconnected-(X2-LCD-Pad1)") (class "Default")
      (node (ref "X2") (pin "1") (pinfunction "LCD_1") (pintype "passive"))
    )
  )
)
